# Receiver.net
KiCad netlist of a schematic drawn in Altium Designer
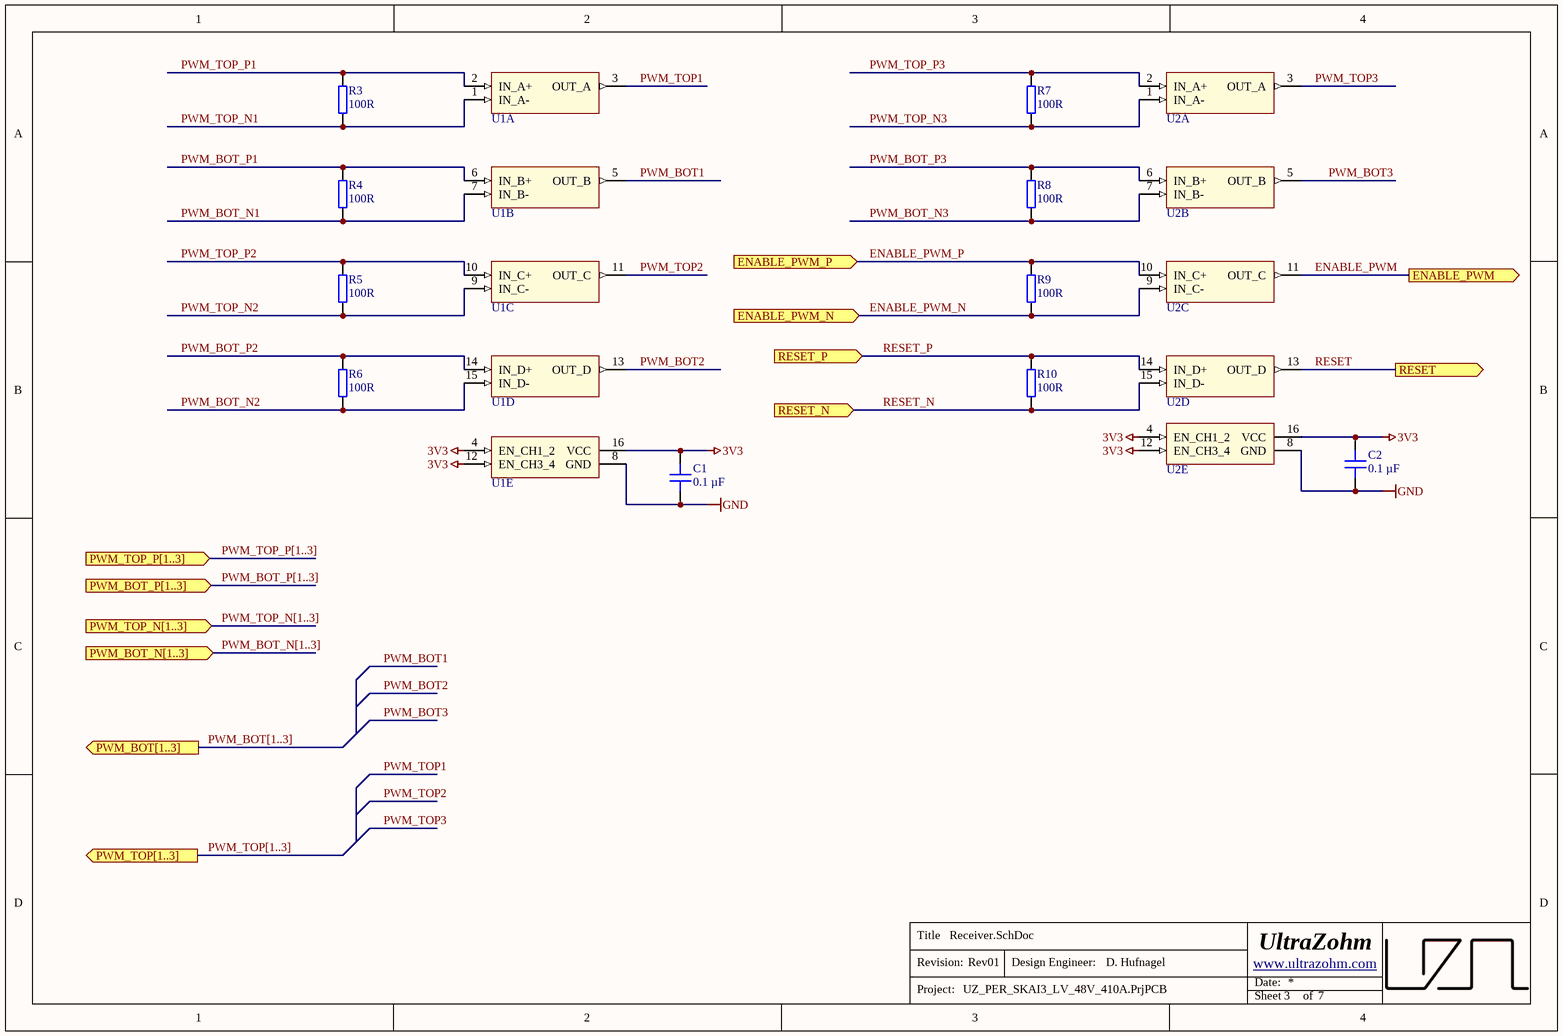
[diagram p0: Receiver.SchDoc]

(export (version "E")
  (design (tool "Eeschema 10.0.6"))
  (components
    (comp (ref "C1")
      (value "0.1 µF")
      (footprint "C_0603")
      (description "Capacitor 0603, 50 VDC, 0.1 µF, X7R")
      (fields
        (field (name "MANUFACTURER PART NUMBER") "C0603X104K5RAC7411")
        (field (name "MANUFACTURER") "KEMET")
        (field (name "CREATED FROM") "MGremer")
      )
      (libsource (lib "user") (part "Capacitor"))
    )
    (comp (ref "C2")
      (value "0.1 µF")
      (footprint "C_0603")
      (description "Capacitor 0603, 50 VDC, 0.1 µF, X7R")
      (fields
        (field (name "MANUFACTURER PART NUMBER") "C0603X104K5RAC7411")
        (field (name "MANUFACTURER") "KEMET")
        (field (name "CREATED FROM") "MGremer")
      )
      (libsource (lib "user") (part "Capacitor"))
    )
    (comp (ref "R3")
      (value "100R")
      (footprint "RES 0603_1608")
      (description "SMD resistor E24 series")
      (fields
        (field (name "MANUFACTURER PART NUMBER") "RK73B1JTTD101J")
        (field (name "MANUFACTURER") "KOA Speer")
        (field (name "CREATED FROM") "MGremer")
      )
      (libsource (lib "user") (part "Resistor"))
    )
    (comp (ref "R4")
      (value "100R")
      (footprint "RES 0603_1608")
      (description "SMD resistor E24 series")
      (fields
        (field (name "MANUFACTURER PART NUMBER") "RK73B1JTTD101J")
        (field (name "MANUFACTURER") "KOA Speer")
        (field (name "CREATED FROM") "MGremer")
      )
      (libsource (lib "user") (part "Resistor"))
    )
    (comp (ref "R5")
      (value "100R")
      (footprint "RES 0603_1608")
      (description "SMD resistor E24 series")
      (fields
        (field (name "MANUFACTURER PART NUMBER") "RK73B1JTTD101J")
        (field (name "MANUFACTURER") "KOA Speer")
        (field (name "CREATED FROM") "MGremer")
      )
      (libsource (lib "user") (part "Resistor"))
    )
    (comp (ref "R6")
      (value "100R")
      (footprint "RES 0603_1608")
      (description "SMD resistor E24 series")
      (fields
        (field (name "MANUFACTURER PART NUMBER") "RK73B1JTTD101J")
        (field (name "MANUFACTURER") "KOA Speer")
        (field (name "CREATED FROM") "MGremer")
      )
      (libsource (lib "user") (part "Resistor"))
    )
    (comp (ref "R7")
      (value "100R")
      (footprint "RES 0603_1608")
      (description "SMD resistor E24 series")
      (fields
        (field (name "MANUFACTURER PART NUMBER") "RK73B1JTTD101J")
        (field (name "MANUFACTURER") "KOA Speer")
        (field (name "CREATED FROM") "MGremer")
      )
      (libsource (lib "user") (part "Resistor"))
    )
    (comp (ref "R8")
      (value "100R")
      (footprint "RES 0603_1608")
      (description "SMD resistor E24 series")
      (fields
        (field (name "MANUFACTURER PART NUMBER") "RK73B1JTTD101J")
        (field (name "MANUFACTURER") "KOA Speer")
        (field (name "CREATED FROM") "MGremer")
      )
      (libsource (lib "user") (part "Resistor"))
    )
    (comp (ref "R9")
      (value "100R")
      (footprint "RES 0603_1608")
      (description "SMD resistor E24 series")
      (fields
        (field (name "MANUFACTURER PART NUMBER") "RK73B1JTTD101J")
        (field (name "MANUFACTURER") "KOA Speer")
        (field (name "CREATED FROM") "MGremer")
      )
      (libsource (lib "user") (part "Resistor"))
    )
    (comp (ref "R10")
      (value "100R")
      (footprint "RES 0603_1608")
      (description "SMD resistor E24 series")
      (fields
        (field (name "MANUFACTURER PART NUMBER") "RK73B1JTTD101J")
        (field (name "MANUFACTURER") "KOA Speer")
        (field (name "CREATED FROM") "MGremer")
      )
      (libsource (lib "user") (part "Resistor"))
    )
    (comp (ref "U1")
      (value "DS34LV86TM/NOPB")
      (footprint "TI_D-R-PDSO-G16_N")
      (description "3V Enhanced CMOS Quad Differential Line Receiver, 16-pin Narrow SOIC, Pb-Free")
      (fields
        (field (name "MANUFACTURER") "Texas Instruments")
        (field (name "LCSC PART NUMBER") "C181570")
        (field (name "CREATED FROM") "D. Hufnagel")
      )
      (libsource (lib "user") (part "DS26LV32ATM"))
    )
    (comp (ref "U2")
      (value "DS34LV86TM/NOPB")
      (footprint "TI_D-R-PDSO-G16_N")
      (description "3V Enhanced CMOS Quad Differential Line Receiver, 16-pin Narrow SOIC, Pb-Free")
      (fields
        (field (name "MANUFACTURER") "Texas Instruments")
        (field (name "LCSC PART NUMBER") "C181570")
        (field (name "CREATED FROM") "D. Hufnagel")
      )
      (libsource (lib "user") (part "DS26LV32ATM"))
    )
  )
  (nets
    (net (code "1") (name "/ENABLE_PWM") (class "Default")
      (node (ref "U2") (pin "11") (pinfunction "OUT_C_11") (pintype "output"))
    )
    (net (code "2") (name "/ENABLE_PWM_N") (class "Default")
      (node (ref "R9") (pin "1") (pinfunction "1_1") (pintype "passive"))
      (node (ref "U2") (pin "9") (pinfunction "IN_C-_9") (pintype "input"))
    )
    (net (code "3") (name "/ENABLE_PWM_P") (class "Default")
      (node (ref "R9") (pin "2") (pinfunction "2_2") (pintype "passive"))
      (node (ref "U2") (pin "10") (pinfunction "IN_C+_10") (pintype "input"))
    )
    (net (code "4") (name "/PWM_BOT1") (class "Default")
      (node (ref "U1") (pin "5") (pinfunction "OUT_B_5") (pintype "output"))
    )
    (net (code "5") (name "/PWM_BOT2") (class "Default")
      (node (ref "U1") (pin "13") (pinfunction "OUT_D_13") (pintype "output"))
    )
    (net (code "6") (name "/PWM_BOT3") (class "Default")
      (node (ref "U2") (pin "5") (pinfunction "OUT_B_5") (pintype "output"))
    )
    (net (code "8") (name "/PWM_BOT_N1") (class "Default")
      (node (ref "R4") (pin "1") (pinfunction "1_1") (pintype "passive"))
      (node (ref "U1") (pin "7") (pinfunction "IN_B-_7") (pintype "input"))
    )
    (net (code "9") (name "/PWM_BOT_N2") (class "Default")
      (node (ref "R6") (pin "1") (pinfunction "1_1") (pintype "passive"))
      (node (ref "U1") (pin "15") (pinfunction "IN_D-_15") (pintype "input"))
    )
    (net (code "10") (name "/PWM_BOT_N3") (class "Default")
      (node (ref "R8") (pin "1") (pinfunction "1_1") (pintype "passive"))
      (node (ref "U2") (pin "7") (pinfunction "IN_B-_7") (pintype "input"))
    )
    (net (code "12") (name "/PWM_BOT_P1") (class "Default")
      (node (ref "R4") (pin "2") (pinfunction "2_2") (pintype "passive"))
      (node (ref "U1") (pin "6") (pinfunction "IN_B+_6") (pintype "input"))
    )
    (net (code "13") (name "/PWM_BOT_P2") (class "Default")
      (node (ref "R6") (pin "2") (pinfunction "2_2") (pintype "passive"))
      (node (ref "U1") (pin "14") (pinfunction "IN_D+_14") (pintype "input"))
    )
    (net (code "14") (name "/PWM_BOT_P3") (class "Default")
      (node (ref "R8") (pin "2") (pinfunction "2_2") (pintype "passive"))
      (node (ref "U2") (pin "6") (pinfunction "IN_B+_6") (pintype "input"))
    )
    (net (code "16") (name "/PWM_TOP1") (class "Default")
      (node (ref "U1") (pin "3") (pinfunction "OUT_A_3") (pintype "output"))
    )
    (net (code "17") (name "/PWM_TOP2") (class "Default")
      (node (ref "U1") (pin "11") (pinfunction "OUT_C_11") (pintype "output"))
    )
    (net (code "18") (name "/PWM_TOP3") (class "Default")
      (node (ref "U2") (pin "3") (pinfunction "OUT_A_3") (pintype "output"))
    )
    (net (code "20") (name "/PWM_TOP_N1") (class "Default")
      (node (ref "R3") (pin "1") (pinfunction "1_1") (pintype "passive"))
      (node (ref "U1") (pin "1") (pinfunction "IN_A-_1") (pintype "input"))
    )
    (net (code "21") (name "/PWM_TOP_N2") (class "Default")
      (node (ref "R5") (pin "1") (pinfunction "1_1") (pintype "passive"))
      (node (ref "U1") (pin "9") (pinfunction "IN_C-_9") (pintype "input"))
    )
    (net (code "22") (name "/PWM_TOP_N3") (class "Default")
      (node (ref "R7") (pin "1") (pinfunction "1_1") (pintype "passive"))
      (node (ref "U2") (pin "1") (pinfunction "IN_A-_1") (pintype "input"))
    )
    (net (code "24") (name "/PWM_TOP_P1") (class "Default")
      (node (ref "R3") (pin "2") (pinfunction "2_2") (pintype "passive"))
      (node (ref "U1") (pin "2") (pinfunction "IN_A+_2") (pintype "input"))
    )
    (net (code "25") (name "/PWM_TOP_P2") (class "Default")
      (node (ref "R5") (pin "2") (pinfunction "2_2") (pintype "passive"))
      (node (ref "U1") (pin "10") (pinfunction "IN_C+_10") (pintype "input"))
    )
    (net (code "26") (name "/PWM_TOP_P3") (class "Default")
      (node (ref "R7") (pin "2") (pinfunction "2_2") (pintype "passive"))
      (node (ref "U2") (pin "2") (pinfunction "IN_A+_2") (pintype "input"))
    )
    (net (code "28") (name "/RESET") (class "Default")
      (node (ref "U2") (pin "13") (pinfunction "OUT_D_13") (pintype "output"))
    )
    (net (code "29") (name "/RESET_N") (class "Default")
      (node (ref "R10") (pin "1") (pinfunction "1_1") (pintype "passive"))
      (node (ref "U2") (pin "15") (pinfunction "IN_D-_15") (pintype "input"))
    )
    (net (code "30") (name "/RESET_P") (class "Default")
      (node (ref "R10") (pin "2") (pinfunction "2_2") (pintype "passive"))
      (node (ref "U2") (pin "14") (pinfunction "IN_D+_14") (pintype "input"))
    )
    (net (code "31") (name "3V3") (class "Default")
      (node (ref "C1") (pin "2") (pinfunction "2_2") (pintype "passive"))
      (node (ref "C2") (pin "2") (pinfunction "2_2") (pintype "passive"))
      (node (ref "U1") (pin "12") (pinfunction "~{EN}_12") (pintype "input"))
      (node (ref "U1") (pin "16") (pinfunction "VCC_16") (pintype "power_in"))
      (node (ref "U1") (pin "4") (pinfunction "EN_4") (pintype "input"))
      (node (ref "U2") (pin "12") (pinfunction "~{EN}_12") (pintype "input"))
      (node (ref "U2") (pin "16") (pinfunction "VCC_16") (pintype "power_in"))
      (node (ref "U2") (pin "4") (pinfunction "EN_4") (pintype "input"))
    )
    (net (code "32") (name "GND") (class "Default")
      (node (ref "C1") (pin "1") (pinfunction "1_1") (pintype "passive"))
      (node (ref "C2") (pin "1") (pinfunction "1_1") (pintype "passive"))
      (node (ref "U1") (pin "8") (pinfunction "GND_8") (pintype "power_in"))
      (node (ref "U2") (pin "8") (pinfunction "GND_8") (pintype "power_in"))
    )
  )
)
